# HighCurrent.net
KiCad netlist of a schematic drawn in Altium Designer
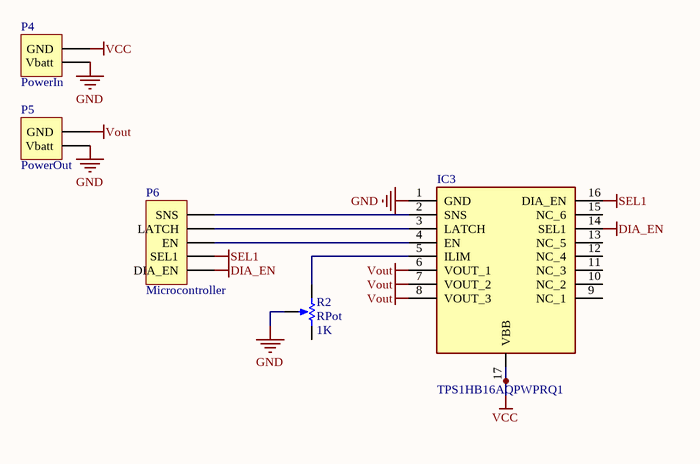
[diagram p0: HighCurrent.SchDoc]

(export (version "E")
  (design (tool "Eeschema 10.0.6"))
  (components
    (comp (ref "IC3")
      (value "TPS1HB16AQPWPRQ1")
      (footprint "SamacSys:SOP65P640X120-17N")
      (description "Integrated Circuit")
      (fields (field (name "MOUSER PART NUMBER") "595-TPS1HB16AQPWPRQ1"))
      (libsource (lib "*") (part "TPS1HB16AQPWPRQ1"))
    )
    (comp (ref "P4")
      (value "PowerIn")
      (footprint "HDR1X2")
      (description "Power Header")
      (fields (field (name "PUBLISHER") "Altium Limited"))
      (libsource (lib "Miscellaneous Connectors") (part "Header 2"))
    )
    (comp (ref "P5")
      (value "PowerOut")
      (footprint "HDR1X2")
      (description "Power Header")
      (fields (field (name "PUBLISHER") "Altium Limited"))
      (libsource (lib "Miscellaneous Connectors") (part "Header 2"))
    )
    (comp (ref "P6")
      (value "Microcontroller")
      (footprint "HDR1X5")
      (description "Header, 5-Pin")
      (fields (field (name "PUBLISHER") "Altium Limited"))
      (libsource (lib "Miscellaneous Connectors") (part "Header 5"))
    )
    (comp (ref "R2")
      (value "RPot")
      (footprint "VR5")
      (description "Potentiometer")
      (fields (field (name "ALTIUM_VALUE") "1K") (field (name "PUBLISHER") "Altium Limited"))
      (libsource (lib "Miscellaneous Devices") (part "RPot"))
    )
  )
  (nets
    (net (code "1") (name "DIA_EN") (class "Default")
      (node (ref "IC3") (pin "14") (pinfunction "SEL1_14") (pintype "passive"))
      (node (ref "P6") (pin "5") (pinfunction "DIA_EN_5") (pintype "passive"))
    )
    (net (code "2") (name "GND") (class "Default")
      (node (ref "IC3") (pin "1") (pinfunction "GND_1") (pintype "passive"))
      (node (ref "P4") (pin "1") (pinfunction "Vbatt_1") (pintype "passive"))
      (node (ref "P5") (pin "1") (pinfunction "Vbatt_1") (pintype "passive"))
      (node (ref "R2") (pin "3") (pinfunction "TAP_3") (pintype "passive"))
    )
    (net (code "3") (name "Net-(IC3-EN)") (class "Default")
      (node (ref "IC3") (pin "4") (pinfunction "EN_4") (pintype "passive"))
      (node (ref "P6") (pin "3") (pinfunction "EN_3") (pintype "passive"))
    )
    (net (code "4") (name "Net-(IC3-ILIM)") (class "Default")
      (node (ref "IC3") (pin "5") (pinfunction "ILIM_5") (pintype "passive"))
      (node (ref "R2") (pin "1") (pinfunction "TOP_1") (pintype "passive"))
    )
    (net (code "5") (name "Net-(IC3-LATCH)") (class "Default")
      (node (ref "IC3") (pin "3") (pinfunction "LATCH_3") (pintype "passive"))
      (node (ref "P6") (pin "2") (pinfunction "LATCH_2") (pintype "passive"))
    )
    (net (code "6") (name "Net-(IC3-SNS)") (class "Default")
      (node (ref "IC3") (pin "2") (pinfunction "SNS_2") (pintype "passive"))
      (node (ref "P6") (pin "1") (pinfunction "SNS_1") (pintype "passive"))
    )
    (net (code "7") (name "SEL1") (class "Default")
      (node (ref "IC3") (pin "16") (pinfunction "DIA_EN_16") (pintype "passive"))
      (node (ref "P6") (pin "4") (pinfunction "SEL1_4") (pintype "passive"))
    )
    (net (code "8") (name "VCC") (class "Default")
      (node (ref "IC3") (pin "17") (pinfunction "VBB_17") (pintype "passive"))
      (node (ref "P4") (pin "2") (pinfunction "GND_2") (pintype "passive"))
    )
    (net (code "9") (name "Vout") (class "Default")
      (node (ref "IC3") (pin "6") (pinfunction "VOUT_1_6") (pintype "passive"))
      (node (ref "IC3") (pin "7") (pinfunction "VOUT_2_7") (pintype "passive"))
      (node (ref "IC3") (pin "8") (pinfunction "VOUT_3_8") (pintype "passive"))
      (node (ref "P5") (pin "2") (pinfunction "GND_2") (pintype "passive"))
    )
    (net (code "10") (name "unconnected-(IC3-NC_1-Pad9)") (class "Default")
      (node (ref "IC3") (pin "9") (pinfunction "NC_1_9") (pintype "passive"))
    )
    (net (code "11") (name "unconnected-(IC3-NC_2-Pad10)") (class "Default")
      (node (ref "IC3") (pin "10") (pinfunction "NC_2_10") (pintype "passive"))
    )
    (net (code "12") (name "unconnected-(IC3-NC_3-Pad11)") (class "Default")
      (node (ref "IC3") (pin "11") (pinfunction "NC_3_11") (pintype "passive"))
    )
    (net (code "13") (name "unconnected-(IC3-NC_4-Pad12)") (class "Default")
      (node (ref "IC3") (pin "12") (pinfunction "NC_4_12") (pintype "passive"))
    )
    (net (code "14") (name "unconnected-(IC3-NC_5-Pad13)") (class "Default")
      (node (ref "IC3") (pin "13") (pinfunction "NC_5_13") (pintype "passive"))
    )
    (net (code "15") (name "unconnected-(IC3-NC_6-Pad15)") (class "Default")
      (node (ref "IC3") (pin "15") (pinfunction "NC_6_15") (pintype "passive"))
    )
    (net (code "16") (name "unconnected-(R2-BOT-Pad2)") (class "Default")
      (node (ref "R2") (pin "2") (pinfunction "BOT_2") (pintype "passive"))
    )
  )
)
